# 02-PowerSupply.net
KiCad netlist of a schematic drawn in Altium Designer
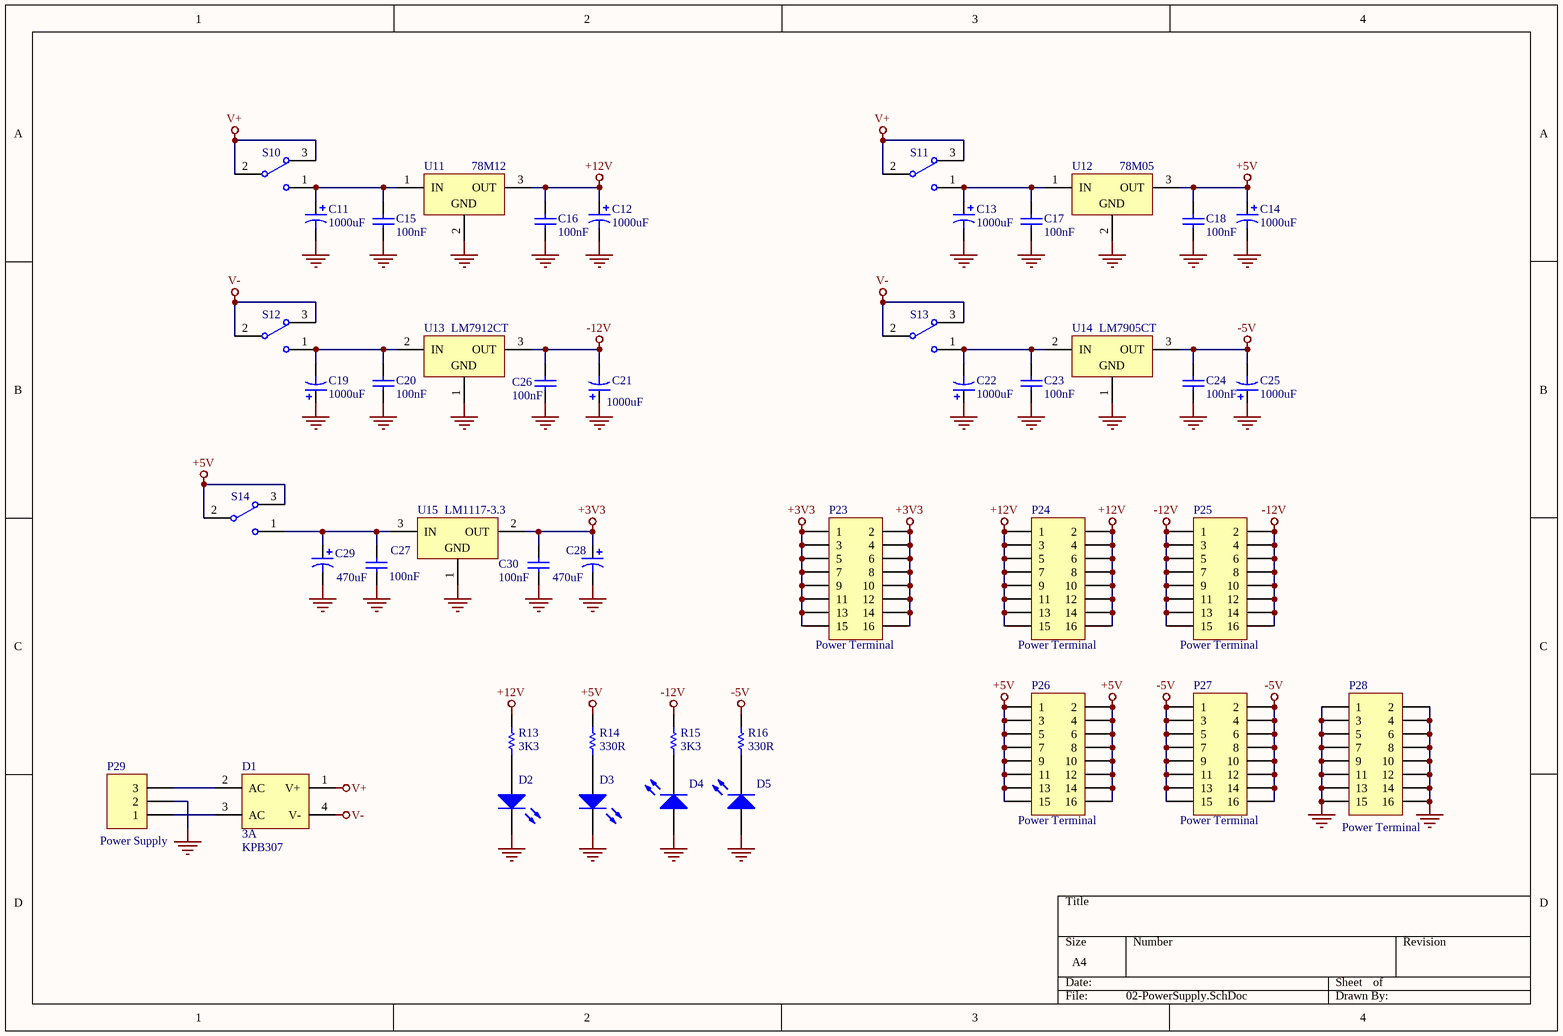
[diagram p0: 02-PowerSupply.SchDoc]

(export (version "E")
  (design (tool "Eeschema 10.0.6"))
  (components
    (comp (ref "C11")
      (value "1000uF")
      (footprint "C-ALU-10x10mm")
      (description "Polarized Capacitor (Radial)")
      (fields (field (name "Comment") "1000uF/25V") (field (name "PUBLISHER") "Altium Limited"))
      (libsource (lib "Miscellaneous Devices") (part "Cap Pol1"))
    )
    (comp (ref "C12")
      (value "1000uF")
      (footprint "C-ALU-10x10mm")
      (description "Polarized Capacitor (Radial)")
      (fields (field (name "Comment") "1000uF/25V") (field (name "PUBLISHER") "Altium Limited"))
      (libsource (lib "Miscellaneous Devices") (part "Cap Pol1"))
    )
    (comp (ref "C13")
      (value "1000uF")
      (footprint "C-ALU-10x10mm")
      (description "Polarized Capacitor (Radial)")
      (fields (field (name "Comment") "1000uF/25V") (field (name "PUBLISHER") "Altium Limited"))
      (libsource (lib "Miscellaneous Devices") (part "Cap Pol1"))
    )
    (comp (ref "C14")
      (value "1000uF")
      (footprint "C-ALU-10x10mm")
      (description "Polarized Capacitor (Radial)")
      (fields (field (name "Comment") "1000uF/25V") (field (name "PUBLISHER") "Altium Limited"))
      (libsource (lib "Miscellaneous Devices") (part "Cap Pol1"))
    )
    (comp (ref "C15")
      (value "100nF")
      (footprint "C-0805")
      (description "Capacitor")
      (fields
        (field (name "MANUFACTURER") "Generic Components")
        (field (name "Comment") "104")
        (field (name "PUBLISHER") "Altium Hobart Technology Centre")
      )
      (libsource (lib "Miscellaneous Devices") (part "Cap"))
    )
    (comp (ref "C16")
      (value "100nF")
      (footprint "C-0805")
      (description "Capacitor")
      (fields
        (field (name "MANUFACTURER") "Generic Components")
        (field (name "Comment") "104")
        (field (name "PUBLISHER") "Altium Hobart Technology Centre")
      )
      (libsource (lib "Miscellaneous Devices") (part "Cap"))
    )
    (comp (ref "C17")
      (value "100nF")
      (footprint "C-0805")
      (description "Capacitor")
      (fields
        (field (name "MANUFACTURER") "Generic Components")
        (field (name "Comment") "104")
        (field (name "PUBLISHER") "Altium Hobart Technology Centre")
      )
      (libsource (lib "Miscellaneous Devices") (part "Cap"))
    )
    (comp (ref "C18")
      (value "100nF")
      (footprint "C-0805")
      (description "Capacitor")
      (fields
        (field (name "MANUFACTURER") "Generic Components")
        (field (name "Comment") "104")
        (field (name "PUBLISHER") "Altium Hobart Technology Centre")
      )
      (libsource (lib "Miscellaneous Devices") (part "Cap"))
    )
    (comp (ref "C19")
      (value "1000uF")
      (footprint "C-ALU-10x10mm")
      (description "Polarized Capacitor (Radial)")
      (fields (field (name "Comment") "1000uF/25V") (field (name "PUBLISHER") "Altium Limited"))
      (libsource (lib "Miscellaneous Devices") (part "Cap Pol1"))
    )
    (comp (ref "C20")
      (value "100nF")
      (footprint "C-0805")
      (description "Capacitor")
      (fields
        (field (name "MANUFACTURER") "Generic Components")
        (field (name "Comment") "104")
        (field (name "PUBLISHER") "Altium Hobart Technology Centre")
      )
      (libsource (lib "Miscellaneous Devices") (part "Cap"))
    )
    (comp (ref "C21")
      (value "1000uF")
      (footprint "C-ALU-10x10mm")
      (description "Polarized Capacitor (Radial)")
      (fields (field (name "Comment") "1000uF/25V") (field (name "PUBLISHER") "Altium Limited"))
      (libsource (lib "Miscellaneous Devices") (part "Cap Pol1"))
    )
    (comp (ref "C22")
      (value "1000uF")
      (footprint "C-ALU-10x10mm")
      (description "Polarized Capacitor (Radial)")
      (fields (field (name "Comment") "1000uF/25V") (field (name "PUBLISHER") "Altium Limited"))
      (libsource (lib "Miscellaneous Devices") (part "Cap Pol1"))
    )
    (comp (ref "C23")
      (value "100nF")
      (footprint "C-0805")
      (description "Capacitor")
      (fields
        (field (name "MANUFACTURER") "Generic Components")
        (field (name "Comment") "104")
        (field (name "PUBLISHER") "Altium Hobart Technology Centre")
      )
      (libsource (lib "Miscellaneous Devices") (part "Cap"))
    )
    (comp (ref "C24")
      (value "100nF")
      (footprint "C-0805")
      (description "Capacitor")
      (fields
        (field (name "MANUFACTURER") "Generic Components")
        (field (name "Comment") "104")
        (field (name "PUBLISHER") "Altium Hobart Technology Centre")
      )
      (libsource (lib "Miscellaneous Devices") (part "Cap"))
    )
    (comp (ref "C25")
      (value "1000uF")
      (footprint "C-ALU-10x10mm")
      (description "Polarized Capacitor (Radial)")
      (fields (field (name "Comment") "1000uF/25V") (field (name "PUBLISHER") "Altium Limited"))
      (libsource (lib "Miscellaneous Devices") (part "Cap Pol1"))
    )
    (comp (ref "C26")
      (value "100nF")
      (footprint "C-0805")
      (description "Capacitor")
      (fields
        (field (name "MANUFACTURER") "Generic Components")
        (field (name "Comment") "104")
        (field (name "PUBLISHER") "Altium Hobart Technology Centre")
      )
      (libsource (lib "Miscellaneous Devices") (part "Cap"))
    )
    (comp (ref "C27")
      (value "100nF")
      (footprint "C-0805")
      (description "Capacitor")
      (fields
        (field (name "MANUFACTURER") "Generic Components")
        (field (name "Comment") "104")
        (field (name "PUBLISHER") "Altium Hobart Technology Centre")
      )
      (libsource (lib "Miscellaneous Devices") (part "Cap"))
    )
    (comp (ref "C28")
      (value "470uF")
      (footprint "C-ALU-10x10mm")
      (description "Polarized Capacitor (Radial)")
      (fields (field (name "Comment") "470uF/16V") (field (name "PUBLISHER") "Altium Limited"))
      (libsource (lib "Miscellaneous Devices") (part "Cap Pol1"))
    )
    (comp (ref "C29")
      (value "470uF")
      (footprint "C-ALU-10x10mm")
      (description "Polarized Capacitor (Radial)")
      (fields (field (name "Comment") "470uF/16V") (field (name "PUBLISHER") "Altium Limited"))
      (libsource (lib "Miscellaneous Devices") (part "Cap Pol1"))
    )
    (comp (ref "C30")
      (value "100nF")
      (footprint "C-0805")
      (description "Capacitor")
      (fields
        (field (name "MANUFACTURER") "Generic Components")
        (field (name "Comment") "104")
        (field (name "PUBLISHER") "Altium Hobart Technology Centre")
      )
      (libsource (lib "Miscellaneous Devices") (part "Cap"))
    )
    (comp (ref "D1")
      (value "KPB307")
      (footprint "D-DB-3A")
      (description "Diode Bridge")
      (fields (field (name "ALTIUM_VALUE") "3A"))
      (libsource (lib "Miscellaneous Devices") (part "Bridge2"))
    )
    (comp (ref "D2")
      (value "LED")
      (footprint "LED-3528")
      (description "Typical INFRARED GaAs LED")
      (fields (field (name "PUBLISHER") "Altium Limited"))
      (libsource (lib "Miscellaneous Devices") (part "LED0"))
    )
    (comp (ref "D3")
      (value "LED")
      (footprint "LED-3528")
      (description "Typical INFRARED GaAs LED")
      (fields (field (name "PUBLISHER") "Altium Limited"))
      (libsource (lib "Miscellaneous Devices") (part "LED0"))
    )
    (comp (ref "D4")
      (value "LED")
      (footprint "LED-3528")
      (description "Typical INFRARED GaAs LED")
      (fields (field (name "PUBLISHER") "Altium Limited"))
      (libsource (lib "Miscellaneous Devices") (part "LED0"))
    )
    (comp (ref "D5")
      (value "LED")
      (footprint "LED-3528")
      (description "Typical INFRARED GaAs LED")
      (fields (field (name "PUBLISHER") "Altium Limited"))
      (libsource (lib "Miscellaneous Devices") (part "LED0"))
    )
    (comp (ref "P23")
      (value "Power Terminal")
      (footprint "HDR2X8")
      (description "Header, 8-Pin, Dual row")
      (fields (field (name "Comment") "Header 8X2"))
      (libsource (lib "Miscellaneous Connectors") (part "Header 8X2"))
    )
    (comp (ref "P24")
      (value "Power Terminal")
      (footprint "HDR2X8")
      (description "Header, 8-Pin, Dual row")
      (fields (field (name "Comment") "Header 8X2"))
      (libsource (lib "Miscellaneous Connectors") (part "Header 8X2"))
    )
    (comp (ref "P25")
      (value "Power Terminal")
      (footprint "HDR2X8")
      (description "Header, 8-Pin, Dual row")
      (fields (field (name "Comment") "Header 8X2"))
      (libsource (lib "Miscellaneous Connectors") (part "Header 8X2"))
    )
    (comp (ref "P26")
      (value "Power Terminal")
      (footprint "HDR2X8")
      (description "Header, 8-Pin, Dual row")
      (fields (field (name "Comment") "Header 8X2"))
      (libsource (lib "Miscellaneous Connectors") (part "Header 8X2"))
    )
    (comp (ref "P27")
      (value "Power Terminal")
      (footprint "HDR2X8")
      (description "Header, 8-Pin, Dual row")
      (fields (field (name "Comment") "Header 8X2"))
      (libsource (lib "Miscellaneous Connectors") (part "Header 8X2"))
    )
    (comp (ref "P28")
      (value "Power Terminal")
      (footprint "HDR2X8")
      (description "Header, 8-Pin, Dual row")
      (fields (field (name "Comment") "Header 8X2"))
      (libsource (lib "Miscellaneous Connectors") (part "Header 8X2"))
    )
    (comp (ref "P29")
      (value "Power Supply")
      (footprint "HDR1X3")
      (description "Header, 3-Pin")
      (fields (field (name "Comment") "H3"))
      (libsource (lib "Miscellaneous Connectors") (part "Header 3"))
    )
    (comp (ref "R13")
      (value "3K3")
      (footprint "C-0805")
      (description "Resistor")
      (fields (field (name "Comment") "332") (field (name "PUBLISHER") "Altium Limited"))
      (libsource (lib "Miscellaneous Devices") (part "Res1"))
    )
    (comp (ref "R14")
      (value "330R")
      (footprint "R-0805")
      (description "Resistor")
      (fields (field (name "Comment") "331") (field (name "PUBLISHER") "Altium Limited"))
      (libsource (lib "Miscellaneous Devices") (part "Res1"))
    )
    (comp (ref "R15")
      (value "3K3")
      (footprint "R-0805")
      (description "Resistor")
      (fields (field (name "Comment") "332") (field (name "PUBLISHER") "Altium Limited"))
      (libsource (lib "Miscellaneous Devices") (part "Res1"))
    )
    (comp (ref "R16")
      (value "330R")
      (footprint "R-0805")
      (description "Resistor")
      (fields (field (name "Comment") "331") (field (name "PUBLISHER") "Altium Limited"))
      (libsource (lib "Miscellaneous Devices") (part "Res1"))
    )
    (comp (ref "S10")
      (value "SW-SPDT")
      (footprint "SW-DIP1SMD")
      (description "SPDT Subminiature Toggle Switch, Right Angle Mounting, Vertical Actuation")
      (fields (field (name "PUBLISHER") "Altium Limited"))
      (libsource (lib "Miscellaneous Devices") (part "SW-SPDT"))
    )
    (comp (ref "S11")
      (value "SW-SPDT")
      (footprint "SW-DIP1SMD")
      (description "SPDT Subminiature Toggle Switch, Right Angle Mounting, Vertical Actuation")
      (fields (field (name "PUBLISHER") "Altium Limited"))
      (libsource (lib "Miscellaneous Devices") (part "SW-SPDT"))
    )
    (comp (ref "S12")
      (value "SW-SPDT")
      (footprint "SW-DIP1SMD")
      (description "SPDT Subminiature Toggle Switch, Right Angle Mounting, Vertical Actuation")
      (fields (field (name "PUBLISHER") "Altium Limited"))
      (libsource (lib "Miscellaneous Devices") (part "SW-SPDT"))
    )
    (comp (ref "S13")
      (value "SW-SPDT")
      (footprint "SW-DIP1SMD")
      (description "SPDT Subminiature Toggle Switch, Right Angle Mounting, Vertical Actuation")
      (fields (field (name "PUBLISHER") "Altium Limited"))
      (libsource (lib "Miscellaneous Devices") (part "SW-SPDT"))
    )
    (comp (ref "S14")
      (value "SW-SPDT")
      (footprint "SW-DIP1SMD")
      (description "SPDT Subminiature Toggle Switch, Right Angle Mounting, Vertical Actuation")
      (fields (field (name "PUBLISHER") "Altium Limited"))
      (libsource (lib "Miscellaneous Devices") (part "SW-SPDT"))
    )
    (comp (ref "U11")
      (value "78M12")
      (footprint "TO-220-2PC")
      (description "3-Terminal Positive Voltage Regulators, 3-pin TO-220")
      (fields
        (field (name "PARTNUMBER") "LM78M05CT")
        (field (name "MANUFACTURER") "National Semiconductor")
        (field (name "PUBLISHER") "Altium Limited")
      )
      (libsource (lib "NSC LDO") (part "LM78M05CT"))
    )
    (comp (ref "U12")
      (value "78M05")
      (footprint "TO-220-2PC")
      (description "3-Terminal Positive Voltage Regulators, 3-pin TO-220")
      (fields
        (field (name "PARTNUMBER") "LM78M05CT")
        (field (name "MANUFACTURER") "National Semiconductor")
        (field (name "PUBLISHER") "Altium Limited")
      )
      (libsource (lib "NSC LDO") (part "LM78M05CT"))
    )
    (comp (ref "U13")
      (value "LM7912CT")
      (footprint "TO-220-2PC")
      (description "3-Terminal Negative Regulators, 3-pin TO-220")
      (fields
        (field (name "PARTNUMBER") "LM79M12CT")
        (field (name "MANUFACTURER") "National Semiconductor")
        (field (name "PUBLISHER") "Altium Limited")
      )
      (libsource (lib "NSC LDO") (part "LM79M12CT"))
    )
    (comp (ref "U14")
      (value "LM7905CT")
      (footprint "TO-220-2PC")
      (description "3-Terminal Negative Regulators, 3-pin TO-220")
      (fields
        (field (name "PARTNUMBER") "LM79M12CT")
        (field (name "MANUFACTURER") "National Semiconductor")
        (field (name "PUBLISHER") "Altium Limited")
      )
      (libsource (lib "NSC LDO") (part "LM79M12CT"))
    )
    (comp (ref "U15")
      (value "LM1117-3.3")
      (footprint "TO-220-2PC")
      (description "800mA Low-Dropout Linear Regulator, 3-pin TO-252")
      (fields
        (field (name "PARTNUMBER") "LM1117IDTX-3.3")
        (field (name "MANUFACTURER") "National Semiconductor")
        (field (name "PUBLISHER") "Altium Limited")
      )
      (libsource (lib "NSC LDO") (part "LM1117IDTX-3.3"))
    )
  )
  (nets
    (net (code "1") (name "+3V3") (class "Default")
      (node (ref "C28") (pin "1") (pinfunction "1_1") (pintype "passive"))
      (node (ref "C30") (pin "2") (pinfunction "2_2") (pintype "passive"))
      (node (ref "P23") (pin "1") (pinfunction "1_1") (pintype "passive"))
      (node (ref "P23") (pin "10") (pinfunction "10_10") (pintype "passive"))
      (node (ref "P23") (pin "11") (pinfunction "11_11") (pintype "passive"))
      (node (ref "P23") (pin "12") (pinfunction "12_12") (pintype "passive"))
      (node (ref "P23") (pin "13") (pinfunction "13_13") (pintype "passive"))
      (node (ref "P23") (pin "14") (pinfunction "14_14") (pintype "passive"))
      (node (ref "P23") (pin "15") (pinfunction "15_15") (pintype "passive"))
      (node (ref "P23") (pin "16") (pinfunction "16_16") (pintype "passive"))
      (node (ref "P23") (pin "2") (pinfunction "2_2") (pintype "passive"))
      (node (ref "P23") (pin "3") (pinfunction "3_3") (pintype "passive"))
      (node (ref "P23") (pin "4") (pinfunction "4_4") (pintype "passive"))
      (node (ref "P23") (pin "5") (pinfunction "5_5") (pintype "passive"))
      (node (ref "P23") (pin "6") (pinfunction "6_6") (pintype "passive"))
      (node (ref "P23") (pin "7") (pinfunction "7_7") (pintype "passive"))
      (node (ref "P23") (pin "8") (pinfunction "8_8") (pintype "passive"))
      (node (ref "P23") (pin "9") (pinfunction "9_9") (pintype "passive"))
      (node (ref "U15") (pin "2") (pinfunction "OUT_2") (pintype "power_in"))
    )
    (net (code "2") (name "+5V") (class "Default")
      (node (ref "C14") (pin "1") (pinfunction "1_1") (pintype "passive"))
      (node (ref "C18") (pin "2") (pinfunction "2_2") (pintype "passive"))
      (node (ref "P26") (pin "1") (pinfunction "1_1") (pintype "passive"))
      (node (ref "P26") (pin "10") (pinfunction "10_10") (pintype "passive"))
      (node (ref "P26") (pin "11") (pinfunction "11_11") (pintype "passive"))
      (node (ref "P26") (pin "12") (pinfunction "12_12") (pintype "passive"))
      (node (ref "P26") (pin "13") (pinfunction "13_13") (pintype "passive"))
      (node (ref "P26") (pin "14") (pinfunction "14_14") (pintype "passive"))
      (node (ref "P26") (pin "15") (pinfunction "15_15") (pintype "passive"))
      (node (ref "P26") (pin "16") (pinfunction "16_16") (pintype "passive"))
      (node (ref "P26") (pin "2") (pinfunction "2_2") (pintype "passive"))
      (node (ref "P26") (pin "3") (pinfunction "3_3") (pintype "passive"))
      (node (ref "P26") (pin "4") (pinfunction "4_4") (pintype "passive"))
      (node (ref "P26") (pin "5") (pinfunction "5_5") (pintype "passive"))
      (node (ref "P26") (pin "6") (pinfunction "6_6") (pintype "passive"))
      (node (ref "P26") (pin "7") (pinfunction "7_7") (pintype "passive"))
      (node (ref "P26") (pin "8") (pinfunction "8_8") (pintype "passive"))
      (node (ref "P26") (pin "9") (pinfunction "9_9") (pintype "passive"))
      (node (ref "R14") (pin "1") (pinfunction "1_1") (pintype "passive"))
      (node (ref "S14") (pin "2") (pinfunction "2_2") (pintype "passive"))
      (node (ref "S14") (pin "3") (pinfunction "3_3") (pintype "passive"))
      (node (ref "U12") (pin "3") (pinfunction "OUT_3") (pintype "power_in"))
    )
    (net (code "3") (name "+12V") (class "Default")
      (node (ref "C12") (pin "1") (pinfunction "1_1") (pintype "passive"))
      (node (ref "C16") (pin "2") (pinfunction "2_2") (pintype "passive"))
      (node (ref "P24") (pin "1") (pinfunction "1_1") (pintype "passive"))
      (node (ref "P24") (pin "10") (pinfunction "10_10") (pintype "passive"))
      (node (ref "P24") (pin "11") (pinfunction "11_11") (pintype "passive"))
      (node (ref "P24") (pin "12") (pinfunction "12_12") (pintype "passive"))
      (node (ref "P24") (pin "13") (pinfunction "13_13") (pintype "passive"))
      (node (ref "P24") (pin "14") (pinfunction "14_14") (pintype "passive"))
      (node (ref "P24") (pin "15") (pinfunction "15_15") (pintype "passive"))
      (node (ref "P24") (pin "16") (pinfunction "16_16") (pintype "passive"))
      (node (ref "P24") (pin "2") (pinfunction "2_2") (pintype "passive"))
      (node (ref "P24") (pin "3") (pinfunction "3_3") (pintype "passive"))
      (node (ref "P24") (pin "4") (pinfunction "4_4") (pintype "passive"))
      (node (ref "P24") (pin "5") (pinfunction "5_5") (pintype "passive"))
      (node (ref "P24") (pin "6") (pinfunction "6_6") (pintype "passive"))
      (node (ref "P24") (pin "7") (pinfunction "7_7") (pintype "passive"))
      (node (ref "P24") (pin "8") (pinfunction "8_8") (pintype "passive"))
      (node (ref "P24") (pin "9") (pinfunction "9_9") (pintype "passive"))
      (node (ref "R13") (pin "1") (pinfunction "1_1") (pintype "passive"))
      (node (ref "U11") (pin "3") (pinfunction "OUT_3") (pintype "power_in"))
    )
    (net (code "4") (name "-5V") (class "Default")
      (node (ref "C24") (pin "2") (pinfunction "2_2") (pintype "passive"))
      (node (ref "C25") (pin "2") (pinfunction "2_2") (pintype "passive"))
      (node (ref "P27") (pin "1") (pinfunction "1_1") (pintype "passive"))
      (node (ref "P27") (pin "10") (pinfunction "10_10") (pintype "passive"))
      (node (ref "P27") (pin "11") (pinfunction "11_11") (pintype "passive"))
      (node (ref "P27") (pin "12") (pinfunction "12_12") (pintype "passive"))
      (node (ref "P27") (pin "13") (pinfunction "13_13") (pintype "passive"))
      (node (ref "P27") (pin "14") (pinfunction "14_14") (pintype "passive"))
      (node (ref "P27") (pin "15") (pinfunction "15_15") (pintype "passive"))
      (node (ref "P27") (pin "16") (pinfunction "16_16") (pintype "passive"))
      (node (ref "P27") (pin "2") (pinfunction "2_2") (pintype "passive"))
      (node (ref "P27") (pin "3") (pinfunction "3_3") (pintype "passive"))
      (node (ref "P27") (pin "4") (pinfunction "4_4") (pintype "passive"))
      (node (ref "P27") (pin "5") (pinfunction "5_5") (pintype "passive"))
      (node (ref "P27") (pin "6") (pinfunction "6_6") (pintype "passive"))
      (node (ref "P27") (pin "7") (pinfunction "7_7") (pintype "passive"))
      (node (ref "P27") (pin "8") (pinfunction "8_8") (pintype "passive"))
      (node (ref "P27") (pin "9") (pinfunction "9_9") (pintype "passive"))
      (node (ref "R16") (pin "1") (pinfunction "1_1") (pintype "passive"))
      (node (ref "U14") (pin "3") (pinfunction "OUT_3") (pintype "power_in"))
    )
    (net (code "5") (name "-12V") (class "Default")
      (node (ref "C21") (pin "2") (pinfunction "2_2") (pintype "passive"))
      (node (ref "C26") (pin "2") (pinfunction "2_2") (pintype "passive"))
      (node (ref "P25") (pin "1") (pinfunction "1_1") (pintype "passive"))
      (node (ref "P25") (pin "10") (pinfunction "10_10") (pintype "passive"))
      (node (ref "P25") (pin "11") (pinfunction "11_11") (pintype "passive"))
      (node (ref "P25") (pin "12") (pinfunction "12_12") (pintype "passive"))
      (node (ref "P25") (pin "13") (pinfunction "13_13") (pintype "passive"))
      (node (ref "P25") (pin "14") (pinfunction "14_14") (pintype "passive"))
      (node (ref "P25") (pin "15") (pinfunction "15_15") (pintype "passive"))
      (node (ref "P25") (pin "16") (pinfunction "16_16") (pintype "passive"))
      (node (ref "P25") (pin "2") (pinfunction "2_2") (pintype "passive"))
      (node (ref "P25") (pin "3") (pinfunction "3_3") (pintype "passive"))
      (node (ref "P25") (pin "4") (pinfunction "4_4") (pintype "passive"))
      (node (ref "P25") (pin "5") (pinfunction "5_5") (pintype "passive"))
      (node (ref "P25") (pin "6") (pinfunction "6_6") (pintype "passive"))
      (node (ref "P25") (pin "7") (pinfunction "7_7") (pintype "passive"))
      (node (ref "P25") (pin "8") (pinfunction "8_8") (pintype "passive"))
      (node (ref "P25") (pin "9") (pinfunction "9_9") (pintype "passive"))
      (node (ref "R15") (pin "1") (pinfunction "1_1") (pintype "passive"))
      (node (ref "U13") (pin "3") (pinfunction "OUT_3") (pintype "power_in"))
    )
    (net (code "6") (name "GND") (class "Default")
      (node (ref "C11") (pin "2") (pinfunction "2_2") (pintype "passive"))
      (node (ref "C12") (pin "2") (pinfunction "2_2") (pintype "passive"))
      (node (ref "C13") (pin "2") (pinfunction "2_2") (pintype "passive"))
      (node (ref "C14") (pin "2") (pinfunction "2_2") (pintype "passive"))
      (node (ref "C15") (pin "1") (pinfunction "1_1") (pintype "passive"))
      (node (ref "C16") (pin "1") (pinfunction "1_1") (pintype "passive"))
      (node (ref "C17") (pin "1") (pinfunction "1_1") (pintype "passive"))
      (node (ref "C18") (pin "1") (pinfunction "1_1") (pintype "passive"))
      (node (ref "C19") (pin "1") (pinfunction "1_1") (pintype "passive"))
      (node (ref "C20") (pin "1") (pinfunction "1_1") (pintype "passive"))
      (node (ref "C21") (pin "1") (pinfunction "1_1") (pintype "passive"))
      (node (ref "C22") (pin "1") (pinfunction "1_1") (pintype "passive"))
      (node (ref "C23") (pin "1") (pinfunction "1_1") (pintype "passive"))
      (node (ref "C24") (pin "1") (pinfunction "1_1") (pintype "passive"))
      (node (ref "C25") (pin "1") (pinfunction "1_1") (pintype "passive"))
      (node (ref "C26") (pin "1") (pinfunction "1_1") (pintype "passive"))
      (node (ref "C27") (pin "1") (pinfunction "1_1") (pintype "passive"))
      (node (ref "C28") (pin "2") (pinfunction "2_2") (pintype "passive"))
      (node (ref "C29") (pin "2") (pinfunction "2_2") (pintype "passive"))
      (node (ref "C30") (pin "1") (pinfunction "1_1") (pintype "passive"))
      (node (ref "D2") (pin "2") (pinfunction "K_2") (pintype "passive"))
      (node (ref "D3") (pin "2") (pinfunction "K_2") (pintype "passive"))
      (node (ref "D4") (pin "1") (pinfunction "A_1") (pintype "passive"))
      (node (ref "D5") (pin "1") (pinfunction "A_1") (pintype "passive"))
      (node (ref "P28") (pin "1") (pinfunction "1_1") (pintype "passive"))
      (node (ref "P28") (pin "10") (pinfunction "10_10") (pintype "passive"))
      (node (ref "P28") (pin "11") (pinfunction "11_11") (pintype "passive"))
      (node (ref "P28") (pin "12") (pinfunction "12_12") (pintype "passive"))
      (node (ref "P28") (pin "13") (pinfunction "13_13") (pintype "passive"))
      (node (ref "P28") (pin "14") (pinfunction "14_14") (pintype "passive"))
      (node (ref "P28") (pin "15") (pinfunction "15_15") (pintype "passive"))
      (node (ref "P28") (pin "16") (pinfunction "16_16") (pintype "passive"))
      (node (ref "P28") (pin "2") (pinfunction "2_2") (pintype "passive"))
      (node (ref "P28") (pin "3") (pinfunction "3_3") (pintype "passive"))
      (node (ref "P28") (pin "4") (pinfunction "4_4") (pintype "passive"))
      (node (ref "P28") (pin "5") (pinfunction "5_5") (pintype "passive"))
      (node (ref "P28") (pin "6") (pinfunction "6_6") (pintype "passive"))
      (node (ref "P28") (pin "7") (pinfunction "7_7") (pintype "passive"))
      (node (ref "P28") (pin "8") (pinfunction "8_8") (pintype "passive"))
      (node (ref "P28") (pin "9") (pinfunction "9_9") (pintype "passive"))
      (node (ref "P29") (pin "2") (pinfunction "2_2") (pintype "passive"))
      (node (ref "U11") (pin "2") (pinfunction "GND_2") (pintype "power_in"))
      (node (ref "U12") (pin "2") (pinfunction "GND_2") (pintype "power_in"))
      (node (ref "U13") (pin "1") (pinfunction "GND_1") (pintype "power_in"))
      (node (ref "U14") (pin "1") (pinfunction "GND_1") (pintype "power_in"))
      (node (ref "U15") (pin "1") (pinfunction "GND_1") (pintype "power_in"))
    )
    (net (code "7") (name "Net-(D1-AC-Pad2)") (class "Default")
      (node (ref "D1") (pin "2") (pinfunction "AC_2") (pintype "passive"))
      (node (ref "P29") (pin "3") (pinfunction "3_3") (pintype "passive"))
    )
    (net (code "8") (name "Net-(D1-AC-Pad3)") (class "Default")
      (node (ref "D1") (pin "3") (pinfunction "AC_3") (pintype "passive"))
      (node (ref "P29") (pin "1") (pinfunction "1_1") (pintype "passive"))
    )
    (net (code "9") (name "Net-(D2-A)") (class "Default")
      (node (ref "D2") (pin "1") (pinfunction "A_1") (pintype "passive"))
      (node (ref "R13") (pin "2") (pinfunction "2_2") (pintype "passive"))
    )
    (net (code "10") (name "Net-(D3-A)") (class "Default")
      (node (ref "D3") (pin "1") (pinfunction "A_1") (pintype "passive"))
      (node (ref "R14") (pin "2") (pinfunction "2_2") (pintype "passive"))
    )
    (net (code "11") (name "Net-(D4-K)") (class "Default")
      (node (ref "D4") (pin "2") (pinfunction "K_2") (pintype "passive"))
      (node (ref "R15") (pin "2") (pinfunction "2_2") (pintype "passive"))
    )
    (net (code "12") (name "Net-(D5-K)") (class "Default")
      (node (ref "D5") (pin "2") (pinfunction "K_2") (pintype "passive"))
      (node (ref "R16") (pin "2") (pinfunction "2_2") (pintype "passive"))
    )
    (net (code "13") (name "Net-(U11-IN)") (class "Default")
      (node (ref "C11") (pin "1") (pinfunction "1_1") (pintype "passive"))
      (node (ref "C15") (pin "2") (pinfunction "2_2") (pintype "passive"))
      (node (ref "S10") (pin "1") (pinfunction "1_1") (pintype "passive"))
      (node (ref "U11") (pin "1") (pinfunction "IN_1") (pintype "power_in"))
    )
    (net (code "14") (name "Net-(U12-IN)") (class "Default")
      (node (ref "C13") (pin "1") (pinfunction "1_1") (pintype "passive"))
      (node (ref "C17") (pin "2") (pinfunction "2_2") (pintype "passive"))
      (node (ref "S11") (pin "1") (pinfunction "1_1") (pintype "passive"))
      (node (ref "U12") (pin "1") (pinfunction "IN_1") (pintype "power_in"))
    )
    (net (code "15") (name "Net-(U13-IN)") (class "Default")
      (node (ref "C19") (pin "2") (pinfunction "2_2") (pintype "passive"))
      (node (ref "C20") (pin "2") (pinfunction "2_2") (pintype "passive"))
      (node (ref "S12") (pin "1") (pinfunction "1_1") (pintype "passive"))
      (node (ref "U13") (pin "2") (pinfunction "IN_2") (pintype "power_in"))
    )
    (net (code "16") (name "Net-(U14-IN)") (class "Default")
      (node (ref "C22") (pin "2") (pinfunction "2_2") (pintype "passive"))
      (node (ref "C23") (pin "2") (pinfunction "2_2") (pintype "passive"))
      (node (ref "S13") (pin "1") (pinfunction "1_1") (pintype "passive"))
      (node (ref "U14") (pin "2") (pinfunction "IN_2") (pintype "power_in"))
    )
    (net (code "17") (name "Net-(U15-IN)") (class "Default")
      (node (ref "C27") (pin "2") (pinfunction "2_2") (pintype "passive"))
      (node (ref "C29") (pin "1") (pinfunction "1_1") (pintype "passive"))
      (node (ref "S14") (pin "1") (pinfunction "1_1") (pintype "passive"))
      (node (ref "U15") (pin "3") (pinfunction "IN_3") (pintype "power_in"))
    )
    (net (code "18") (name "V+") (class "Default")
      (node (ref "D1") (pin "1") (pinfunction "V+_1") (pintype "passive"))
      (node (ref "S10") (pin "2") (pinfunction "2_2") (pintype "passive"))
      (node (ref "S10") (pin "3") (pinfunction "3_3") (pintype "passive"))
      (node (ref "S11") (pin "2") (pinfunction "2_2") (pintype "passive"))
      (node (ref "S11") (pin "3") (pinfunction "3_3") (pintype "passive"))
    )
    (net (code "19") (name "V-") (class "Default")
      (node (ref "D1") (pin "4") (pinfunction "V-_4") (pintype "passive"))
      (node (ref "S12") (pin "2") (pinfunction "2_2") (pintype "passive"))
      (node (ref "S12") (pin "3") (pinfunction "3_3") (pintype "passive"))
      (node (ref "S13") (pin "2") (pinfunction "2_2") (pintype "passive"))
      (node (ref "S13") (pin "3") (pinfunction "3_3") (pintype "passive"))
    )
  )
)
